# Audio_Amp.net
KiCad netlist of a schematic drawn in Altium Designer
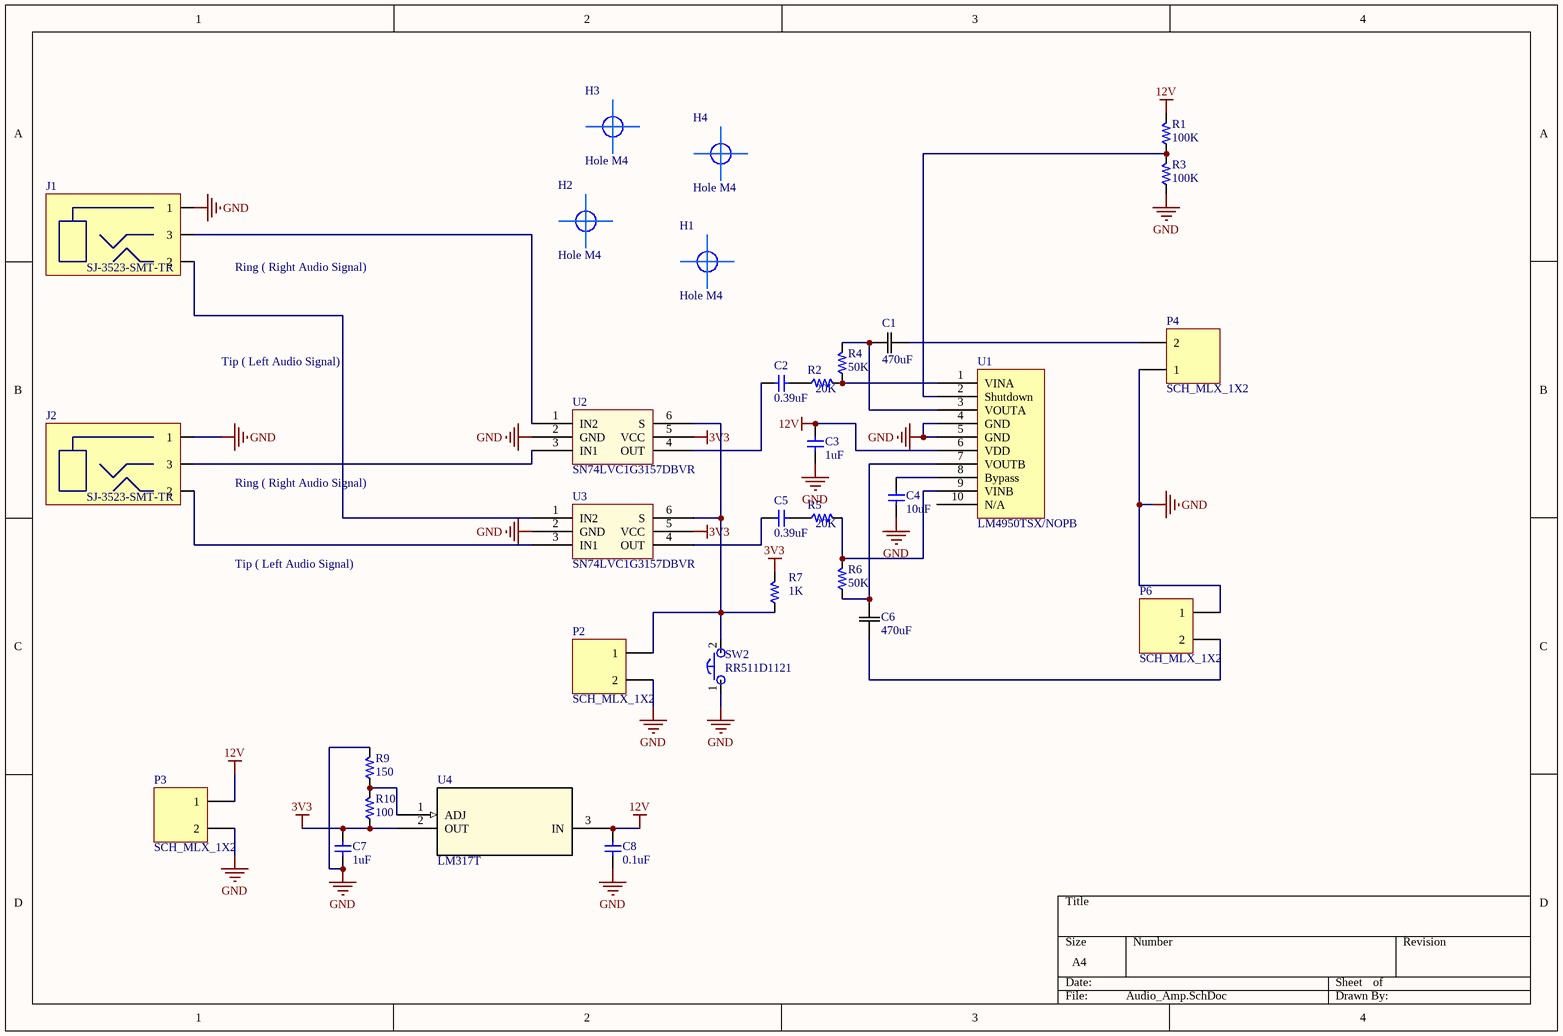
[diagram p0: Audio_Amp.SchDoc]

(export (version "E")
  (design (tool "Eeschema 10.0.6"))
  (components
    (comp (ref "C1")
      (value "470uF")
      (footprint "CAP_PAN_10X12.5")
      (description "Imported")
      (fields (field (name "MANUFACTURER_PART_NUMBER") "EEU-FR1E471B"))
      (libsource (lib "470uF Electrolytic Cap") (part "EEU-FR1E471B"))
    )
    (comp (ref "C2")
      (value "0.39uF")
      (footprint "PCB_GENERIC_SMD_0603")
      (description "CAP CER 0603 0.39uF 16V X5R 20%")
      (fields (field (name "TOLERANCE") "20%") (field (name "VOLTAGE") "16V"))
      (libsource (lib "CAP-0603") (part "C060-000U39-00"))
    )
    (comp (ref "C3")
      (value "1uF")
      (footprint "PCB_GENERIC_SMD_0603")
      (description "CAP CER 0603 0.39uF 16V X5R 20%")
      (fields (field (name "TOLERANCE") "20%") (field (name "VOLTAGE") "16V"))
      (libsource (lib "CAP-0603") (part "C060-000U39-00"))
    )
    (comp (ref "C4")
      (value "10uF")
      (footprint "PCB_GENERIC_SMD_0603")
      (description "CAP CER 0603 0.39uF 16V X5R 20%")
      (fields (field (name "TOLERANCE") "20%") (field (name "VOLTAGE") "16V"))
      (libsource (lib "CAP-0603") (part "C060-000U39-00"))
    )
    (comp (ref "C5")
      (value "0.39uF")
      (footprint "PCB_GENERIC_SMD_0603")
      (description "CAP CER 0603 0.39uF 16V X5R 20%")
      (fields (field (name "TOLERANCE") "20%") (field (name "VOLTAGE") "16V"))
      (libsource (lib "CAP-0603") (part "C060-000U39-00"))
    )
    (comp (ref "C6")
      (value "470uF")
      (footprint "CAP_PAN_10X12.5")
      (description "Imported")
      (fields (field (name "MANUFACTURER_PART_NUMBER") "EEU-FR1E471B"))
      (libsource (lib "470uF Electrolytic Cap") (part "EEU-FR1E471B"))
    )
    (comp (ref "C7")
      (value "1uF")
      (footprint "PCB_GENERIC_SMD_0603")
      (description "CAP CER 0603 0.39uF 16V X5R 20%")
      (fields (field (name "TOLERANCE") "20%") (field (name "VOLTAGE") "16V"))
      (libsource (lib "CAP-0603") (part "C060-000U39-00"))
    )
    (comp (ref "C8")
      (value "0.1uF")
      (footprint "PCB_GENERIC_SMD_0603")
      (description "CAP CER 0603 0.39uF 16V X5R 20%")
      (fields (field (name "TOLERANCE") "20%") (field (name "VOLTAGE") "16V"))
      (libsource (lib "CAP-0603") (part "C060-000U39-00"))
    )
    (comp (ref "H1") (value "Hole M4") (footprint "#10Hole") (libsource (lib "#10Hole") (part "#10Hole")))
    (comp (ref "H2") (value "Hole M4") (footprint "#10Hole") (libsource (lib "#10Hole") (part "#10Hole")))
    (comp (ref "H3") (value "Hole M4") (footprint "#10Hole") (libsource (lib "#10Hole") (part "#10Hole")))
    (comp (ref "H4") (value "Hole M4") (footprint "#10Hole") (libsource (lib "#10Hole") (part "#10Hole")))
    (comp (ref "J1")
      (value "SJ-3523-SMT-TR")
      (footprint "CUI_SJ-3523-SMT-TR")
      (description "CONN JACK STEREO 3.5MM")
      (libsource (lib "SJ-3523-SMT-TR") (part "SJ-3523-SMT-TR"))
    )
    (comp (ref "J2")
      (value "SJ-3523-SMT-TR")
      (footprint "CUI_SJ-3523-SMT-TR")
      (description "CONN JACK STEREO 3.5MM")
      (libsource (lib "SJ-3523-SMT-TR") (part "SJ-3523-SMT-TR"))
    )
    (comp (ref "P2")
      (value "SCH_MLX_1X2")
      (footprint "PCB_MLX_MICROFIT_1X2")
      (libsource (lib "Molex Microfit 3.0 1x2") (part "SCH_MLX_1X2"))
    )
    (comp (ref "P3")
      (value "SCH_MLX_1X2")
      (footprint "PCB_MLX_MICROFIT_1X2")
      (libsource (lib "Molex Microfit 3.0 1x2") (part "SCH_MLX_1X2"))
    )
    (comp (ref "P4")
      (value "SCH_MLX_1X2")
      (footprint "PCB_MLX_MICROFIT_1X2")
      (libsource (lib "") (part "SCH_MLX_1X2_1"))
    )
    (comp (ref "P6")
      (value "SCH_MLX_1X2")
      (footprint "PCB_MLX_MICROFIT_1X2")
      (libsource (lib "Molex Microfit 3.0 1x2") (part "SCH_MLX_1X2"))
    )
    (comp (ref "R1")
      (value "100K")
      (footprint "PCB_GENERIC_SMD_0603")
      (description "RES 0603 20K 5% 100mW")
      (fields (field (name "POWER") "100mW") (field (name "TOLERANCE") "1%"))
      (libsource (lib "RES-0603") (part "R060-00203-01"))
    )
    (comp (ref "R2")
      (value "20K")
      (footprint "PCB_GENERIC_SMD_0603")
      (description "RES 0603 20K 5% 100mW")
      (fields (field (name "POWER") "100mW") (field (name "TOLERANCE") "1%"))
      (libsource (lib "RES-0603") (part "R060-00203-01"))
    )
    (comp (ref "R3")
      (value "100K")
      (footprint "PCB_GENERIC_SMD_0603")
      (description "RES 0603 20K 5% 100mW")
      (fields (field (name "POWER") "100mW") (field (name "TOLERANCE") "1%"))
      (libsource (lib "RES-0603") (part "R060-00203-01"))
    )
    (comp (ref "R4")
      (value "50K")
      (footprint "PCB_GENERIC_SMD_0603")
      (description "RES 0603 20K 5% 100mW")
      (fields (field (name "POWER") "100mW") (field (name "TOLERANCE") "1%"))
      (libsource (lib "RES-0603") (part "R060-00203-01"))
    )
    (comp (ref "R5")
      (value "20K")
      (footprint "PCB_GENERIC_SMD_0603")
      (description "RES 0603 20K 5% 100mW")
      (fields (field (name "POWER") "100mW") (field (name "TOLERANCE") "1%"))
      (libsource (lib "RES-0603") (part "R060-00203-01"))
    )
    (comp (ref "R6")
      (value "50K")
      (footprint "PCB_GENERIC_SMD_0603")
      (description "RES 0603 20K 5% 100mW")
      (fields (field (name "POWER") "100mW") (field (name "TOLERANCE") "1%"))
      (libsource (lib "RES-0603") (part "R060-00203-01"))
    )
    (comp (ref "R7")
      (value "1K")
      (footprint "PCB_GENERIC_SMD_0603")
      (description "RES 0603 20K 5% 100mW")
      (fields (field (name "POWER") "100mW") (field (name "TOLERANCE") "1%"))
      (libsource (lib "RES-0603") (part "R060-00203-01"))
    )
    (comp (ref "R9")
      (value "150")
      (footprint "PCB_GENERIC_SMD_0603")
      (description "RES 0603 20K 5% 100mW")
      (fields (field (name "POWER") "100mW") (field (name "TOLERANCE") "1%"))
      (libsource (lib "RES-0603") (part "R060-00203-01"))
    )
    (comp (ref "R10")
      (value "100")
      (footprint "PCB_GENERIC_SMD_0603")
      (description "RES 0603 20K 5% 100mW")
      (fields (field (name "POWER") "100mW") (field (name "TOLERANCE") "1%"))
      (libsource (lib "RES-0603") (part "R060-00203-01"))
    )
    (comp (ref "SW2")
      (value "RR511D1121")
      (footprint "RR511D1121")
      (description "SWITCH ROCKER SPST 20A 125V")
      (libsource (lib "2 Pin Rocker Switch") (part "RR511D1121"))
    )
    (comp (ref "U1")
      (value "LM4950TSX/NOPB")
      (footprint "TS9A")
      (description "IC AMP AUDIO PWR 7.5W AB TO263-9")
      (fields (field (name "DIGIKEY PART #") "LM4950TSX/NOPBCT-ND") (field (name "MANUFACTURER") "TI"))
      (libsource (lib "LM4950 Stereo 3W Audio Amplifier") (part "LM4950TSX/NOPB"))
    )
    (comp (ref "U2")
      (value "SN74LVC1G3157DBVR")
      (footprint "SOT95P280X145-6N")
      (description "1 Circuit IC Switch 2:1 15 Ohm SOT-23-6")
      (fields (field (name "DIGIKEY PART #") "296-14908-1-ND") (field (name "MANUFACTURER") "TI"))
      (libsource (lib "SN74LVC1G3157 Analog Mux") (part "SN74LVC1G3157DBVR"))
    )
    (comp (ref "U3")
      (value "SN74LVC1G3157DBVR")
      (footprint "SOT95P280X145-6N")
      (description "1 Circuit IC Switch 2:1 15 Ohm SOT-23-6")
      (fields (field (name "DIGIKEY PART #") "296-14908-1-ND") (field (name "MANUFACTURER") "TI"))
      (libsource (lib "SN74LVC1G3157 Analog Mux") (part "SN74LVC1G3157DBVR"))
    )
    (comp (ref "U4")
      (value "LM317T")
      (footprint "TO-220")
      (description "IC REG LIN POS ADJ 1.5A TO220AB")
      (libsource (lib "LM317T IC Regulator") (part "LM317T"))
    )
  )
  (nets
    (net (code "1") (name "3V3") (class "Default")
      (node (ref "C7") (pin "2") (pinfunction "2_2") (pintype "passive"))
      (node (ref "R10") (pin "1") (pinfunction "1_1") (pintype "passive"))
      (node (ref "R7") (pin "2") (pinfunction "2_2") (pintype "passive"))
      (node (ref "U2") (pin "5") (pinfunction "VCC_5") (pintype "passive"))
      (node (ref "U3") (pin "5") (pinfunction "VCC_5") (pintype "passive"))
      (node (ref "U4") (pin "2") (pinfunction "OUT_2") (pintype "power_in"))
    )
    (net (code "2") (name "12V") (class "Default")
      (node (ref "C3") (pin "2") (pinfunction "2_2") (pintype "passive"))
      (node (ref "C8") (pin "2") (pinfunction "2_2") (pintype "passive"))
      (node (ref "P3") (pin "1") (pinfunction "1_1") (pintype "passive"))
      (node (ref "R1") (pin "2") (pinfunction "2_2") (pintype "passive"))
      (node (ref "U1") (pin "6") (pinfunction "VDD_6") (pintype "passive"))
      (node (ref "U4") (pin "3") (pinfunction "IN_3") (pintype "power_in"))
    )
    (net (code "3") (name "GND") (class "Default")
      (node (ref "C3") (pin "1") (pinfunction "1_1") (pintype "passive"))
      (node (ref "C4") (pin "1") (pinfunction "1_1") (pintype "passive"))
      (node (ref "C7") (pin "1") (pinfunction "1_1") (pintype "passive"))
      (node (ref "C8") (pin "1") (pinfunction "1_1") (pintype "passive"))
      (node (ref "J1") (pin "1") (pinfunction "1_1") (pintype "passive"))
      (node (ref "J2") (pin "1") (pinfunction "1_1") (pintype "passive"))
      (node (ref "P2") (pin "2") (pinfunction "2_2") (pintype "passive"))
      (node (ref "P3") (pin "2") (pinfunction "2_2") (pintype "passive"))
      (node (ref "P4") (pin "1") (pinfunction "1_1") (pintype "passive"))
      (node (ref "P6") (pin "1") (pinfunction "1_1") (pintype "passive"))
      (node (ref "R3") (pin "1") (pinfunction "1_1") (pintype "passive"))
      (node (ref "R9") (pin "2") (pinfunction "2_2") (pintype "passive"))
      (node (ref "SW2") (pin "1") (pinfunction "1_1") (pintype "passive"))
      (node (ref "U1") (pin "4") (pinfunction "GND_4") (pintype "passive"))
      (node (ref "U1") (pin "5") (pinfunction "GND_5") (pintype "passive"))
      (node (ref "U2") (pin "2") (pinfunction "GND_2") (pintype "passive"))
      (node (ref "U3") (pin "2") (pinfunction "GND_2") (pintype "passive"))
    )
    (net (code "4") (name "Net-(C1-Pad2)") (class "Default")
      (node (ref "C1") (pin "2") (pinfunction "2_2") (pintype "passive"))
      (node (ref "P4") (pin "2") (pinfunction "2_2") (pintype "passive"))
    )
    (net (code "5") (name "Net-(C2-Pad2)") (class "Default")
      (node (ref "C2") (pin "2") (pinfunction "2_2") (pintype "passive"))
      (node (ref "R2") (pin "1") (pinfunction "1_1") (pintype "passive"))
    )
    (net (code "6") (name "Net-(C5-Pad2)") (class "Default")
      (node (ref "C5") (pin "2") (pinfunction "2_2") (pintype "passive"))
      (node (ref "R5") (pin "1") (pinfunction "1_1") (pintype "passive"))
    )
    (net (code "7") (name "Net-(C6-Pad2)") (class "Default")
      (node (ref "C6") (pin "2") (pinfunction "2_2") (pintype "passive"))
      (node (ref "P6") (pin "2") (pinfunction "2_2") (pintype "passive"))
    )
    (net (code "8") (name "Net-(U1-Bypass)") (class "Default")
      (node (ref "C4") (pin "2") (pinfunction "2_2") (pintype "passive"))
      (node (ref "U1") (pin "8") (pinfunction "Bypass_8") (pintype "passive"))
    )
    (net (code "9") (name "Net-(U1-Shutdown)") (class "Default")
      (node (ref "R1") (pin "1") (pinfunction "1_1") (pintype "passive"))
      (node (ref "R3") (pin "2") (pinfunction "2_2") (pintype "passive"))
      (node (ref "U1") (pin "2") (pinfunction "Shutdown_2") (pintype "passive"))
    )
    (net (code "10") (name "Net-(U1-VINA)") (class "Default")
      (node (ref "R2") (pin "2") (pinfunction "2_2") (pintype "passive"))
      (node (ref "R4") (pin "1") (pinfunction "1_1") (pintype "passive"))
      (node (ref "U1") (pin "1") (pinfunction "VINA_1") (pintype "passive"))
    )
    (net (code "11") (name "Net-(U1-VINB)") (class "Default")
      (node (ref "R5") (pin "2") (pinfunction "2_2") (pintype "passive"))
      (node (ref "R6") (pin "2") (pinfunction "2_2") (pintype "passive"))
      (node (ref "U1") (pin "9") (pinfunction "VINB_9") (pintype "passive"))
    )
    (net (code "12") (name "Net-(U1-VOUTA)") (class "Default")
      (node (ref "C1") (pin "1") (pinfunction "1_1") (pintype "passive"))
      (node (ref "R4") (pin "2") (pinfunction "2_2") (pintype "passive"))
      (node (ref "U1") (pin "3") (pinfunction "VOUTA_3") (pintype "passive"))
    )
    (net (code "13") (name "Net-(U1-VOUTB)") (class "Default")
      (node (ref "C6") (pin "1") (pinfunction "1_1") (pintype "passive"))
      (node (ref "R6") (pin "1") (pinfunction "1_1") (pintype "passive"))
      (node (ref "U1") (pin "7") (pinfunction "VOUTB_7") (pintype "passive"))
    )
    (net (code "14") (name "Net-(U2-IN1)") (class "Default")
      (node (ref "J2") (pin "3") (pinfunction "3_3") (pintype "passive"))
      (node (ref "U2") (pin "3") (pinfunction "IN1_3") (pintype "passive"))
    )
    (net (code "15") (name "Net-(U2-IN2)") (class "Default")
      (node (ref "J1") (pin "3") (pinfunction "3_3") (pintype "passive"))
      (node (ref "U2") (pin "1") (pinfunction "IN2_1") (pintype "passive"))
    )
    (net (code "16") (name "Net-(U2-OUT)") (class "Default")
      (node (ref "C2") (pin "1") (pinfunction "1_1") (pintype "passive"))
      (node (ref "U2") (pin "4") (pinfunction "OUT_4") (pintype "passive"))
    )
    (net (code "17") (name "Net-(U2-S)") (class "Default")
      (node (ref "P2") (pin "1") (pinfunction "1_1") (pintype "passive"))
      (node (ref "R7") (pin "1") (pinfunction "1_1") (pintype "passive"))
      (node (ref "SW2") (pin "2") (pinfunction "2_2") (pintype "passive"))
      (node (ref "U2") (pin "6") (pinfunction "S_6") (pintype "passive"))
      (node (ref "U3") (pin "6") (pinfunction "S_6") (pintype "passive"))
    )
    (net (code "18") (name "Net-(U3-IN1)") (class "Default")
      (node (ref "J2") (pin "2") (pinfunction "2_2") (pintype "passive"))
      (node (ref "U3") (pin "3") (pinfunction "IN1_3") (pintype "passive"))
    )
    (net (code "19") (name "Net-(U3-IN2)") (class "Default")
      (node (ref "J1") (pin "2") (pinfunction "2_2") (pintype "passive"))
      (node (ref "U3") (pin "1") (pinfunction "IN2_1") (pintype "passive"))
    )
    (net (code "20") (name "Net-(U3-OUT)") (class "Default")
      (node (ref "C5") (pin "1") (pinfunction "1_1") (pintype "passive"))
      (node (ref "U3") (pin "4") (pinfunction "OUT_4") (pintype "passive"))
    )
    (net (code "21") (name "Net-(U4-ADJ)") (class "Default")
      (node (ref "R10") (pin "2") (pinfunction "2_2") (pintype "passive"))
      (node (ref "R9") (pin "1") (pinfunction "1_1") (pintype "passive"))
      (node (ref "U4") (pin "1") (pinfunction "ADJ_1") (pintype "input"))
    )
    (net (code "22") (name "unconnected-(U1-N{slash}A-Pad10)") (class "Default")
      (node (ref "U1") (pin "10") (pinfunction "N/A_10") (pintype "passive"))
    )
  )
)
